# ai_ft232rl_breakout.net
KiCad netlist of a schematic drawn in EAGLE
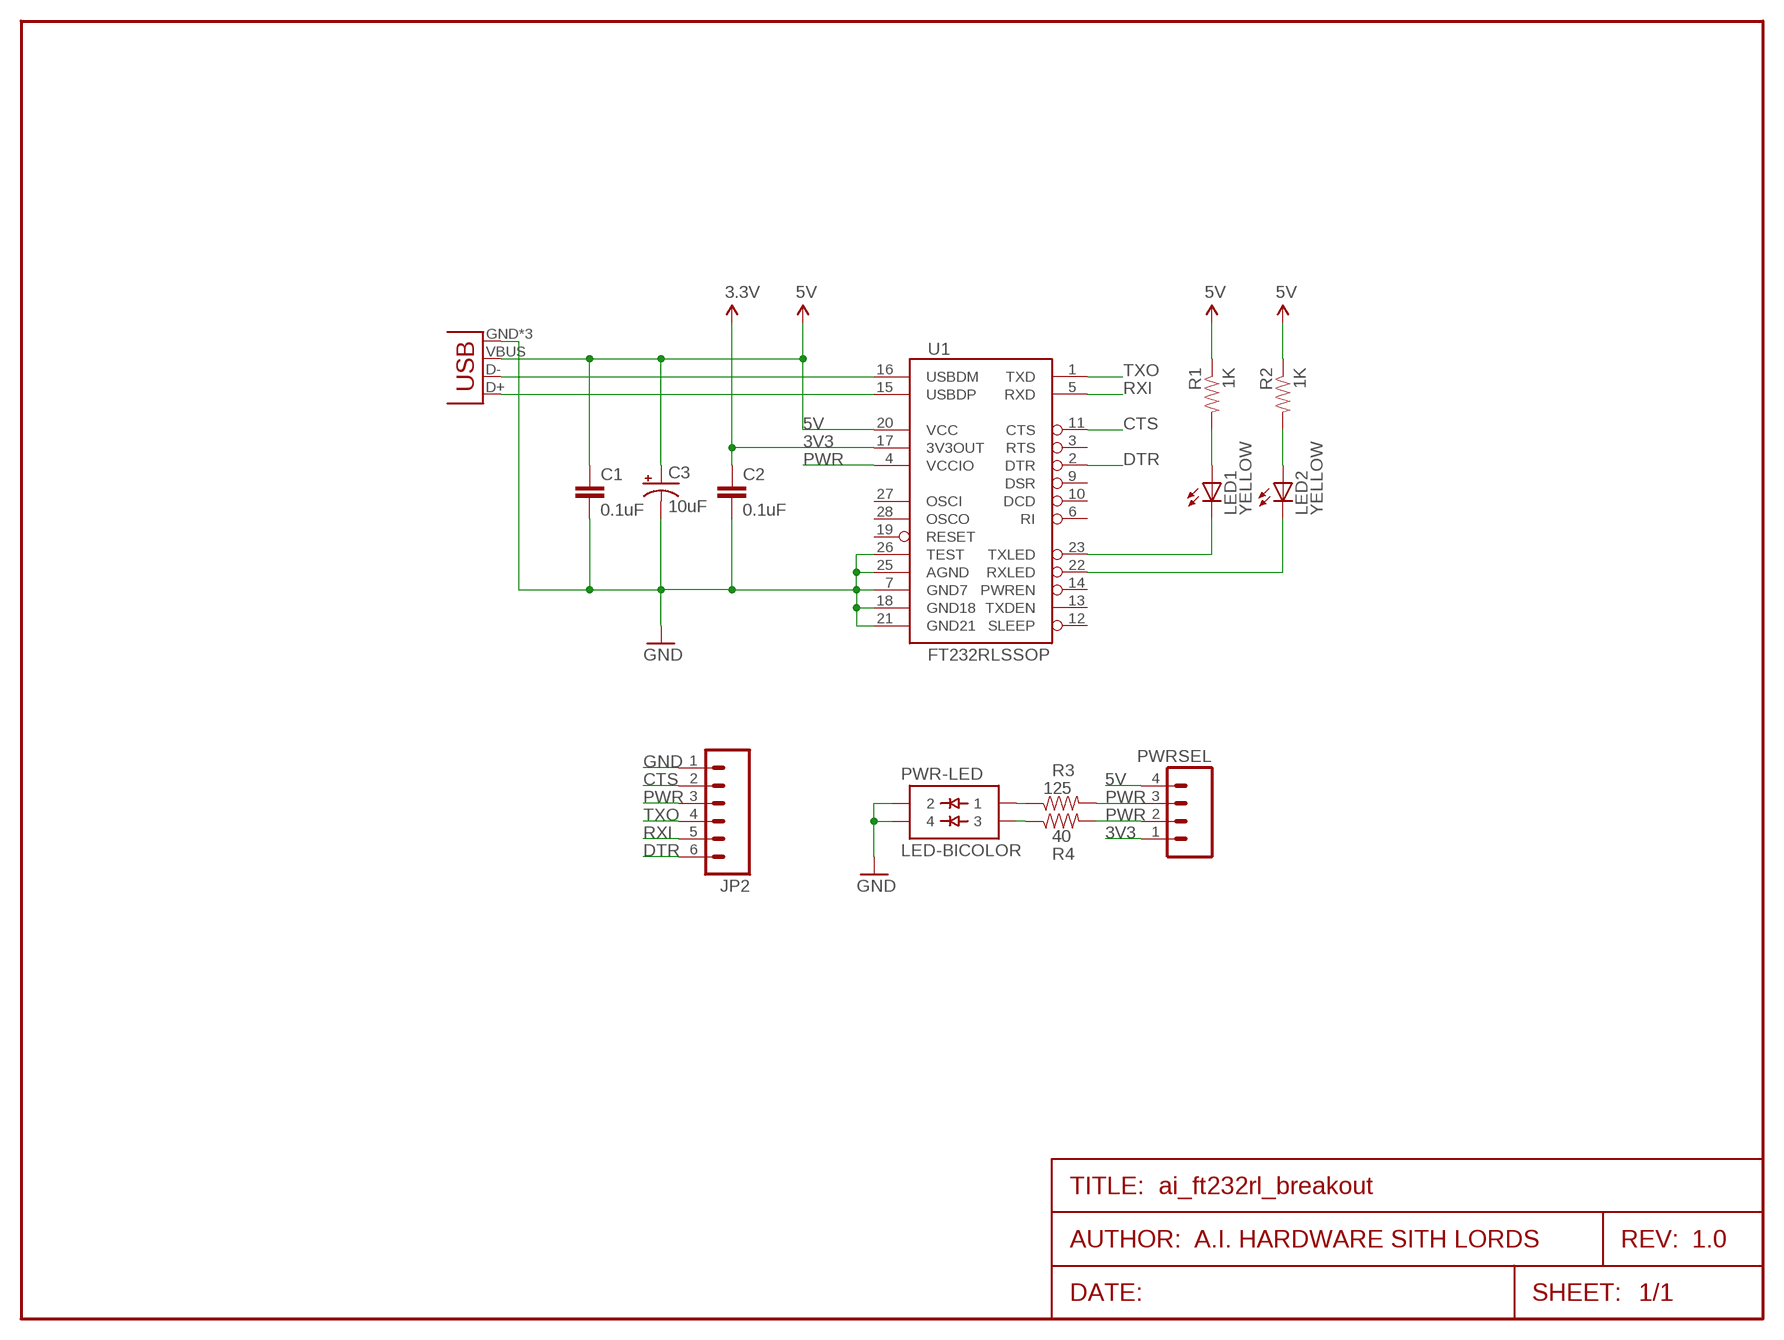
[diagram p0: schematic, sheet 1]

(export (version "E")
  (design (tool "Eeschema 10.0.6"))
  (components
    (comp (ref "C1")
      (value "0.1uF")
      (footprint "eagle-import:0805")
      (libsource (lib "eagle-import") (part "CAP0805"))
    )
    (comp (ref "C2")
      (value "0.1uF")
      (footprint "eagle-import:0805")
      (libsource (lib "eagle-import") (part "CAP0805"))
    )
    (comp (ref "C3")
      (value "10uF")
      (footprint "eagle-import:EIA3216-KIT")
      (libsource (lib "eagle-import") (part "CAP_POL1206-KIT"))
    )
    (comp (ref "JP2")
      (value "M06LONGPADS")
      (footprint "eagle-import:1X06_LONGPADS")
      (libsource (lib "eagle-import") (part "M06LONGPADS"))
    )
    (comp (ref "LED1")
      (value "YELLOW")
      (footprint "eagle-import:LED-0603")
      (libsource (lib "eagle-import") (part "LED-RED0603"))
    )
    (comp (ref "LED2")
      (value "YELLOW")
      (footprint "eagle-import:LED-0603")
      (libsource (lib "eagle-import") (part "LED-GREEN0603"))
    )
    (comp (ref "PWR-LED")
      (value "LED-BICOLOR")
      (footprint "eagle-import:LED-BICOLOR-SMD")
      (libsource (lib "eagle-import") (part "LED-BICOLOR"))
    )
    (comp (ref "PWRSEL")
      (value "M04PTH")
      (footprint "eagle-import:1X04")
      (libsource (lib "eagle-import") (part "M04PTH"))
    )
    (comp (ref "R1")
      (value "1K")
      (footprint "eagle-import:0805")
      (libsource (lib "eagle-import") (part "RESISTOR0805-RES"))
    )
    (comp (ref "R2")
      (value "1K")
      (footprint "eagle-import:0805")
      (libsource (lib "eagle-import") (part "RESISTOR0805-RES"))
    )
    (comp (ref "R3")
      (value "125")
      (footprint "eagle-import:0805")
      (libsource (lib "eagle-import") (part "RESISTOR0805-RES"))
    )
    (comp (ref "R4")
      (value "40")
      (footprint "eagle-import:0805")
      (libsource (lib "eagle-import") (part "RESISTOR0805-RES"))
    )
    (comp (ref "U1")
      (value "FT232RLSSOP")
      (footprint "eagle-import:SSOP28DB")
      (libsource (lib "eagle-import") (part "FT232RLSSOP"))
    )
    (comp (ref "USB")
      (value "USB-MICROB")
      (footprint "eagle-import:USB-MICROB")
      (libsource (lib "eagle-import") (part "USB-MICROB"))
    )
  )
  (nets
    (net (code "1") (name "/CTS") (class "Default")
      (node (ref "JP2") (pin "2") (pinfunction "2_2") (pintype "passive"))
      (node (ref "U1") (pin "11") (pinfunction "CTS_11") (pintype "input"))
    )
    (net (code "2") (name "/DTR") (class "Default")
      (node (ref "JP2") (pin "6") (pinfunction "6_6") (pintype "passive"))
      (node (ref "U1") (pin "2") (pinfunction "DTR_2") (pintype "output"))
    )
    (net (code "3") (name "/PWR") (class "Default")
      (node (ref "JP2") (pin "3") (pinfunction "3_3") (pintype "passive"))
      (node (ref "PWRSEL") (pin "2") (pinfunction "2_2") (pintype "passive"))
      (node (ref "R4") (pin "2") (pinfunction "2_2") (pintype "passive"))
      (node (ref "U1") (pin "4") (pinfunction "VCCIO_4") (pintype "power_in"))
    )
    (net (code "4") (name "/RXI") (class "Default")
      (node (ref "JP2") (pin "5") (pinfunction "5_5") (pintype "passive"))
      (node (ref "U1") (pin "5") (pinfunction "RXD_5") (pintype "input"))
    )
    (net (code "5") (name "/TXO") (class "Default")
      (node (ref "JP2") (pin "4") (pinfunction "4_4") (pintype "passive"))
      (node (ref "U1") (pin "1") (pinfunction "TXD_1") (pintype "output"))
    )
    (net (code "6") (name "3.3V") (class "Default")
      (node (ref "C2") (pin "1") (pinfunction "1_1") (pintype "passive"))
      (node (ref "PWRSEL") (pin "1") (pinfunction "1_1") (pintype "passive"))
      (node (ref "U1") (pin "17") (pinfunction "3V3OUT_17") (pintype "output"))
    )
    (net (code "7") (name "5V") (class "Default")
      (node (ref "C1") (pin "1") (pinfunction "1_1") (pintype "passive"))
      (node (ref "C3") (pin "A") (pinfunction "+_A") (pintype "passive"))
      (node (ref "PWRSEL") (pin "4") (pinfunction "4_4") (pintype "passive"))
      (node (ref "R1") (pin "1") (pinfunction "1_1") (pintype "passive"))
      (node (ref "R2") (pin "1") (pinfunction "1_1") (pintype "passive"))
      (node (ref "U1") (pin "20") (pinfunction "VCC_20") (pintype "power_in"))
      (node (ref "USB") (pin "VBUS") (pinfunction "VBUS_VBUS") (pintype "bidirectional"))
    )
    (net (code "8") (name "GND") (class "Default")
      (node (ref "C1") (pin "2") (pinfunction "2_2") (pintype "passive"))
      (node (ref "C2") (pin "2") (pinfunction "2_2") (pintype "passive"))
      (node (ref "C3") (pin "C") (pinfunction "-_C") (pintype "passive"))
      (node (ref "JP2") (pin "1") (pinfunction "1_1") (pintype "passive"))
      (node (ref "PWR-LED") (pin "2") (pinfunction "2_2") (pintype "bidirectional"))
      (node (ref "PWR-LED") (pin "4") (pinfunction "4_4") (pintype "bidirectional"))
      (node (ref "U1") (pin "18") (pinfunction "GND18_18") (pintype "power_in"))
      (node (ref "U1") (pin "21") (pinfunction "GND21_21") (pintype "power_in"))
      (node (ref "U1") (pin "25") (pinfunction "AGND_25") (pintype "power_in"))
      (node (ref "U1") (pin "26") (pinfunction "TEST_26") (pintype "input"))
      (node (ref "U1") (pin "7") (pinfunction "GND7_7") (pintype "power_in"))
      (node (ref "USB") (pin "GND") (pinfunction "GND_GND") (pintype "bidirectional"))
      (node (ref "USB") (pin "MT1") (pinfunction "GND_MT1") (pintype "bidirectional"))
      (node (ref "USB") (pin "MT2") (pinfunction "GND_MT2") (pintype "bidirectional"))
    )
    (net (code "9") (name "Net-(LED1-PadA)") (class "Default")
      (node (ref "LED1") (pin "A") (pinfunction "A_A") (pintype "passive"))
      (node (ref "R1") (pin "2") (pinfunction "2_2") (pintype "passive"))
    )
    (net (code "10") (name "Net-(LED2-PadA)") (class "Default")
      (node (ref "LED2") (pin "A") (pinfunction "A_A") (pintype "passive"))
      (node (ref "R2") (pin "2") (pinfunction "2_2") (pintype "passive"))
    )
    (net (code "11") (name "Net-(PWR-LED-Pad1)") (class "Default")
      (node (ref "PWR-LED") (pin "1") (pinfunction "1_1") (pintype "bidirectional"))
      (node (ref "R3") (pin "1") (pinfunction "1_1") (pintype "passive"))
    )
    (net (code "12") (name "Net-(PWR-LED-Pad3)") (class "Default")
      (node (ref "PWR-LED") (pin "3") (pinfunction "3_3") (pintype "bidirectional"))
      (node (ref "R4") (pin "1") (pinfunction "1_1") (pintype "passive"))
    )
    (net (code "13") (name "Net-(PWRSEL-Pad3)") (class "Default")
      (node (ref "PWRSEL") (pin "3") (pinfunction "3_3") (pintype "passive"))
      (node (ref "R3") (pin "2") (pinfunction "2_2") (pintype "passive"))
    )
    (net (code "14") (name "Net-(U1-RXLED)") (class "Default")
      (node (ref "LED2") (pin "C") (pinfunction "C_C") (pintype "passive"))
      (node (ref "U1") (pin "22") (pinfunction "RXLED_22") (pintype "input"))
    )
    (net (code "15") (name "Net-(U1-TXLED)") (class "Default")
      (node (ref "LED1") (pin "C") (pinfunction "C_C") (pintype "passive"))
      (node (ref "U1") (pin "23") (pinfunction "TXLED_23") (pintype "input"))
    )
    (net (code "16") (name "Net-(U1-USBDM)") (class "Default")
      (node (ref "U1") (pin "16") (pinfunction "USBDM_16") (pintype "bidirectional"))
      (node (ref "USB") (pin "D-") (pinfunction "D-_D-") (pintype "bidirectional"))
    )
    (net (code "17") (name "Net-(U1-USBDP)") (class "Default")
      (node (ref "U1") (pin "15") (pinfunction "USBDP_15") (pintype "bidirectional"))
      (node (ref "USB") (pin "D+") (pinfunction "D+_D+") (pintype "bidirectional"))
    )
    (net (code "18") (name "unconnected-(U1-DCD-Pad10)") (class "Default")
      (node (ref "U1") (pin "10") (pinfunction "DCD_10") (pintype "input"))
    )
    (net (code "19") (name "unconnected-(U1-DSR-Pad9)") (class "Default")
      (node (ref "U1") (pin "9") (pinfunction "DSR_9") (pintype "input"))
    )
    (net (code "20") (name "unconnected-(U1-OSCI-Pad27)") (class "Default")
      (node (ref "U1") (pin "27") (pinfunction "OSCI_27") (pintype "input"))
    )
    (net (code "21") (name "unconnected-(U1-OSCO-Pad28)") (class "Default")
      (node (ref "U1") (pin "28") (pinfunction "OSCO_28") (pintype "output"))
    )
    (net (code "22") (name "unconnected-(U1-PWREN-Pad14)") (class "Default")
      (node (ref "U1") (pin "14") (pinfunction "PWREN_14") (pintype "input"))
    )
    (net (code "23") (name "unconnected-(U1-RESET-Pad19)") (class "Default")
      (node (ref "U1") (pin "19") (pinfunction "RESET_19") (pintype "input"))
    )
    (net (code "24") (name "unconnected-(U1-RI-Pad6)") (class "Default")
      (node (ref "U1") (pin "6") (pinfunction "RI_6") (pintype "input"))
    )
    (net (code "25") (name "unconnected-(U1-RTS-Pad3)") (class "Default")
      (node (ref "U1") (pin "3") (pinfunction "RTS_3") (pintype "output"))
    )
    (net (code "26") (name "unconnected-(U1-SLEEP-Pad12)") (class "Default")
      (node (ref "U1") (pin "12") (pinfunction "SLEEP_12") (pintype "input"))
    )
    (net (code "27") (name "unconnected-(U1-TXDEN-Pad13)") (class "Default")
      (node (ref "U1") (pin "13") (pinfunction "TXDEN_13") (pintype "input"))
    )
  )
)
